# design.net
KiCad netlist of a schematic drawn in EAGLE
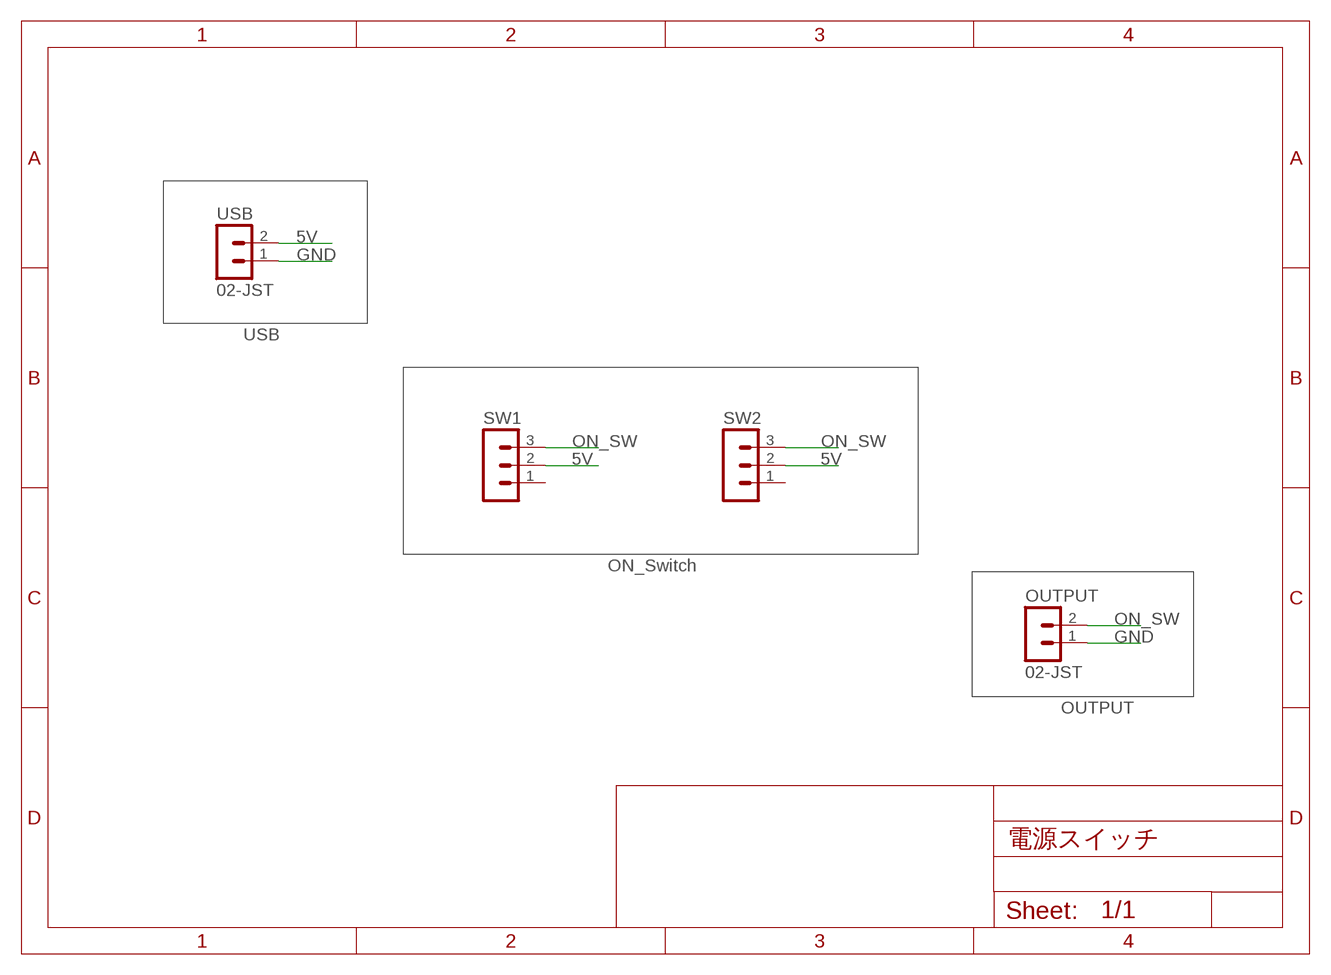
[diagram p0: schematic, sheet 1]

(export (version "E")
  (design (tool "Eeschema 10.0.6"))
  (components
    (comp (ref "OUTPUT")
      (value "02-JST")
      (footprint "eagle-import:B2B-XH")
      (libsource (lib "eagle-import") (part "02-JST"))
    )
    (comp (ref "SW1")
      (value "03-JST")
      (footprint "eagle-import:B3B-XH")
      (libsource (lib "eagle-import") (part "03-JST"))
    )
    (comp (ref "SW2")
      (value "03-JST")
      (footprint "eagle-import:B3B-XH")
      (libsource (lib "eagle-import") (part "03-JST"))
    )
    (comp (ref "USB")
      (value "02-JST")
      (footprint "eagle-import:B2B-XH")
      (libsource (lib "eagle-import") (part "02-JST"))
    )
  )
  (nets
    (net (code "1") (name "/5V") (class "Default")
      (node (ref "SW1") (pin "2") (pinfunction "2_2") (pintype "passive"))
      (node (ref "SW2") (pin "2") (pinfunction "2_2") (pintype "passive"))
      (node (ref "USB") (pin "2") (pinfunction "2_2") (pintype "passive"))
    )
    (net (code "2") (name "/GND") (class "Default")
      (node (ref "OUTPUT") (pin "1") (pinfunction "1_1") (pintype "passive"))
      (node (ref "USB") (pin "1") (pinfunction "1_1") (pintype "passive"))
    )
    (net (code "3") (name "/ON_SW") (class "Default")
      (node (ref "OUTPUT") (pin "2") (pinfunction "2_2") (pintype "passive"))
      (node (ref "SW1") (pin "3") (pinfunction "3_3") (pintype "passive"))
      (node (ref "SW2") (pin "3") (pinfunction "3_3") (pintype "passive"))
    )
    (net (code "4") (name "unconnected-(SW1-Pad1)") (class "Default")
      (node (ref "SW1") (pin "1") (pinfunction "1_1") (pintype "passive"))
    )
    (net (code "5") (name "unconnected-(SW2-Pad1)") (class "Default")
      (node (ref "SW2") (pin "1") (pinfunction "1_1") (pintype "passive"))
    )
  )
)
